# RightBar3_SchDoc.net
KiCad netlist of a schematic drawn in Altium Designer
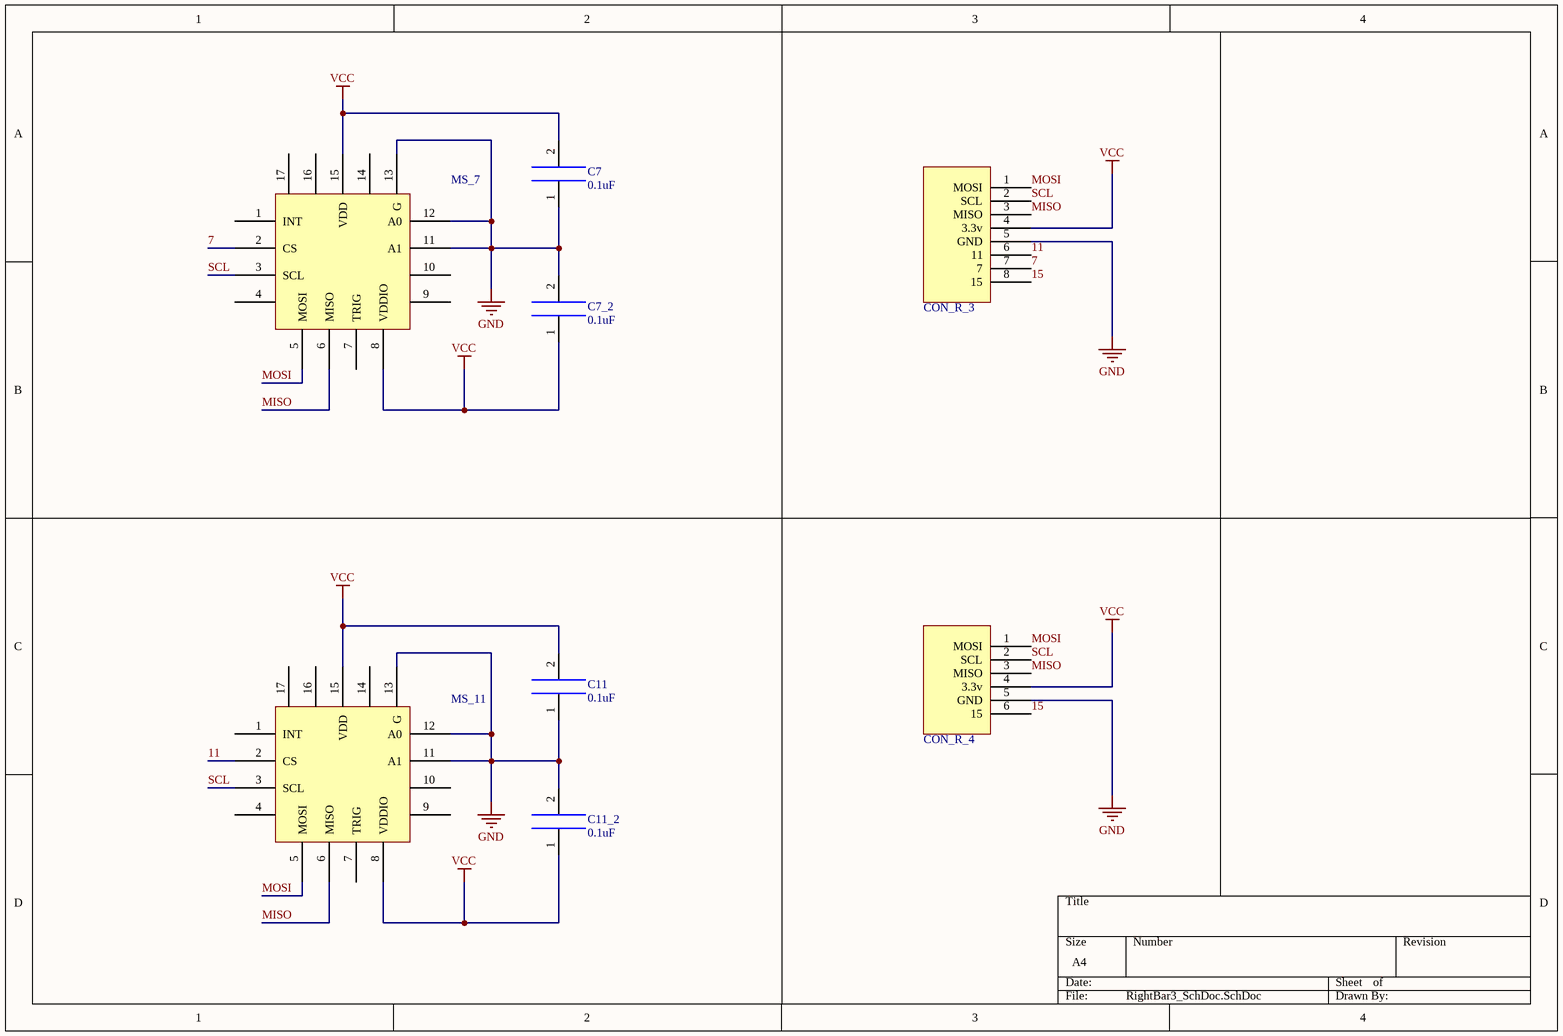
[diagram p0: RightBar3_SchDoc.SchDoc]

(export (version "E")
  (design (tool "Eeschema 10.0.6"))
  (components
    (comp (ref "C7")
      (value "0.1uF")
      (footprint "CAP_0603")
      (description "Capacitance")
      (libsource (lib "MagWaySchlib") (part "CAP"))
    )
    (comp (ref "C7_2")
      (value "0.1uF")
      (footprint "CAP_0603")
      (description "Capacitance")
      (libsource (lib "MagWaySchlib") (part "CAP"))
    )
    (comp (ref "C11")
      (value "0.1uF")
      (footprint "CAP_0603")
      (description "Capacitance")
      (libsource (lib "MagWaySchlib") (part "CAP"))
    )
    (comp (ref "C11_2")
      (value "0.1uF")
      (footprint "CAP_0603")
      (description "Capacitance")
      (libsource (lib "MagWaySchlib") (part "CAP"))
    )
    (comp (ref "CON_R_3")
      (value "PIN_right")
      (footprint "PIN_RIGHT_3")
      (libsource (lib "MagWaySchlib") (part "PIN_right_3"))
    )
    (comp (ref "CON_R_4")
      (value "PIN_right")
      (footprint "PIN_RIGHT_4")
      (libsource (lib "MagWaySchlib") (part "PIN_right_4"))
    )
    (comp (ref "MS_7")
      (value "MLX90393SLW ABA 011 RE")
      (footprint "MLX90393")
      (description "MLX90393 Sensor")
      (libsource (lib "MagWaySchlib") (part "MLX90393SLW ABA 011 RE"))
    )
    (comp (ref "MS_11")
      (value "MLX90393SLW ABA 011 RE")
      (footprint "MLX90393")
      (description "MLX90393 Sensor")
      (libsource (lib "MagWaySchlib") (part "MLX90393SLW ABA 011 RE"))
    )
  )
  (nets
    (net (code "1") (name "/7") (class "Default")
      (node (ref "CON_R_3") (pin "7") (pinfunction "7_7") (pintype "passive"))
      (node (ref "MS_7") (pin "2") (pinfunction "CS_2") (pintype "passive"))
    )
    (net (code "2") (name "/11") (class "Default")
      (node (ref "CON_R_3") (pin "6") (pinfunction "11_6") (pintype "passive"))
      (node (ref "MS_11") (pin "2") (pinfunction "CS_2") (pintype "passive"))
    )
    (net (code "3") (name "/15") (class "Default")
      (node (ref "CON_R_3") (pin "8") (pinfunction "15_8") (pintype "passive"))
      (node (ref "CON_R_4") (pin "6") (pinfunction "15_6") (pintype "passive"))
    )
    (net (code "4") (name "/MISO") (class "Default")
      (node (ref "CON_R_3") (pin "3") (pinfunction "MISO_3") (pintype "passive"))
      (node (ref "CON_R_4") (pin "3") (pinfunction "MISO_3") (pintype "passive"))
      (node (ref "MS_11") (pin "6") (pinfunction "MISO_6") (pintype "passive"))
      (node (ref "MS_7") (pin "6") (pinfunction "MISO_6") (pintype "passive"))
    )
    (net (code "5") (name "/MOSI") (class "Default")
      (node (ref "CON_R_3") (pin "1") (pinfunction "MOSI_1") (pintype "passive"))
      (node (ref "CON_R_4") (pin "1") (pinfunction "MOSI_1") (pintype "passive"))
      (node (ref "MS_11") (pin "5") (pinfunction "MOSI_5") (pintype "passive"))
      (node (ref "MS_7") (pin "5") (pinfunction "MOSI_5") (pintype "passive"))
    )
    (net (code "6") (name "/SCL") (class "Default")
      (node (ref "CON_R_3") (pin "2") (pinfunction "SCL_2") (pintype "passive"))
      (node (ref "CON_R_4") (pin "2") (pinfunction "SCL_2") (pintype "passive"))
      (node (ref "MS_11") (pin "3") (pinfunction "SCL_3") (pintype "passive"))
      (node (ref "MS_7") (pin "3") (pinfunction "SCL_3") (pintype "passive"))
    )
    (net (code "7") (name "GND") (class "Default")
      (node (ref "C11") (pin "1") (pintype "passive"))
      (node (ref "C11_2") (pin "2") (pintype "passive"))
      (node (ref "C7") (pin "1") (pintype "passive"))
      (node (ref "C7_2") (pin "2") (pintype "passive"))
      (node (ref "CON_R_3") (pin "5") (pinfunction "GND_5") (pintype "passive"))
      (node (ref "CON_R_4") (pin "5") (pinfunction "GND_5") (pintype "passive"))
      (node (ref "MS_11") (pin "11") (pinfunction "A1_11") (pintype "passive"))
      (node (ref "MS_11") (pin "12") (pinfunction "A0_12") (pintype "passive"))
      (node (ref "MS_11") (pin "13") (pinfunction "G_13") (pintype "passive"))
      (node (ref "MS_7") (pin "11") (pinfunction "A1_11") (pintype "passive"))
      (node (ref "MS_7") (pin "12") (pinfunction "A0_12") (pintype "passive"))
      (node (ref "MS_7") (pin "13") (pinfunction "G_13") (pintype "passive"))
    )
    (net (code "8") (name "VCC") (class "Default")
      (node (ref "C11") (pin "2") (pintype "passive"))
      (node (ref "C11_2") (pin "1") (pintype "passive"))
      (node (ref "C7") (pin "2") (pintype "passive"))
      (node (ref "C7_2") (pin "1") (pintype "passive"))
      (node (ref "CON_R_3") (pin "4") (pinfunction "3.3v_4") (pintype "passive"))
      (node (ref "CON_R_4") (pin "4") (pinfunction "3.3v_4") (pintype "passive"))
      (node (ref "MS_11") (pin "15") (pinfunction "VDD_15") (pintype "passive"))
      (node (ref "MS_11") (pin "8") (pinfunction "VDDIO_8") (pintype "passive"))
      (node (ref "MS_7") (pin "15") (pinfunction "VDD_15") (pintype "passive"))
      (node (ref "MS_7") (pin "8") (pinfunction "VDDIO_8") (pintype "passive"))
    )
    (net (code "9") (name "unconnected-(MS_7-INT-Pad1)") (class "Default")
      (node (ref "MS_7") (pin "1") (pinfunction "INT_1") (pintype "passive"))
    )
    (net (code "10") (name "unconnected-(MS_7-Pad4)") (class "Default")
      (node (ref "MS_7") (pin "4") (pintype "passive"))
    )
    (net (code "11") (name "unconnected-(MS_7-Pad9)") (class "Default")
      (node (ref "MS_7") (pin "9") (pintype "passive"))
    )
    (net (code "12") (name "unconnected-(MS_7-Pad10)") (class "Default")
      (node (ref "MS_7") (pin "10") (pintype "passive"))
    )
    (net (code "13") (name "unconnected-(MS_7-Pad14)") (class "Default")
      (node (ref "MS_7") (pin "14") (pintype "passive"))
    )
    (net (code "14") (name "unconnected-(MS_7-Pad16)") (class "Default")
      (node (ref "MS_7") (pin "16") (pintype "passive"))
    )
    (net (code "15") (name "unconnected-(MS_7-Pad17)") (class "Default")
      (node (ref "MS_7") (pin "17") (pintype "passive"))
    )
    (net (code "16") (name "unconnected-(MS_7-TRIG-Pad7)") (class "Default")
      (node (ref "MS_7") (pin "7") (pinfunction "TRIG_7") (pintype "passive"))
    )
    (net (code "17") (name "unconnected-(MS_11-INT-Pad1)") (class "Default")
      (node (ref "MS_11") (pin "1") (pinfunction "INT_1") (pintype "passive"))
    )
    (net (code "18") (name "unconnected-(MS_11-Pad4)") (class "Default")
      (node (ref "MS_11") (pin "4") (pintype "passive"))
    )
    (net (code "19") (name "unconnected-(MS_11-Pad9)") (class "Default")
      (node (ref "MS_11") (pin "9") (pintype "passive"))
    )
    (net (code "20") (name "unconnected-(MS_11-Pad10)") (class "Default")
      (node (ref "MS_11") (pin "10") (pintype "passive"))
    )
    (net (code "21") (name "unconnected-(MS_11-Pad14)") (class "Default")
      (node (ref "MS_11") (pin "14") (pintype "passive"))
    )
    (net (code "22") (name "unconnected-(MS_11-Pad16)") (class "Default")
      (node (ref "MS_11") (pin "16") (pintype "passive"))
    )
    (net (code "23") (name "unconnected-(MS_11-Pad17)") (class "Default")
      (node (ref "MS_11") (pin "17") (pintype "passive"))
    )
    (net (code "24") (name "unconnected-(MS_11-TRIG-Pad7)") (class "Default")
      (node (ref "MS_11") (pin "7") (pinfunction "TRIG_7") (pintype "passive"))
    )
  )
)
